# Receive_V1_Sch.net
KiCad netlist of a schematic drawn in Altium Designer
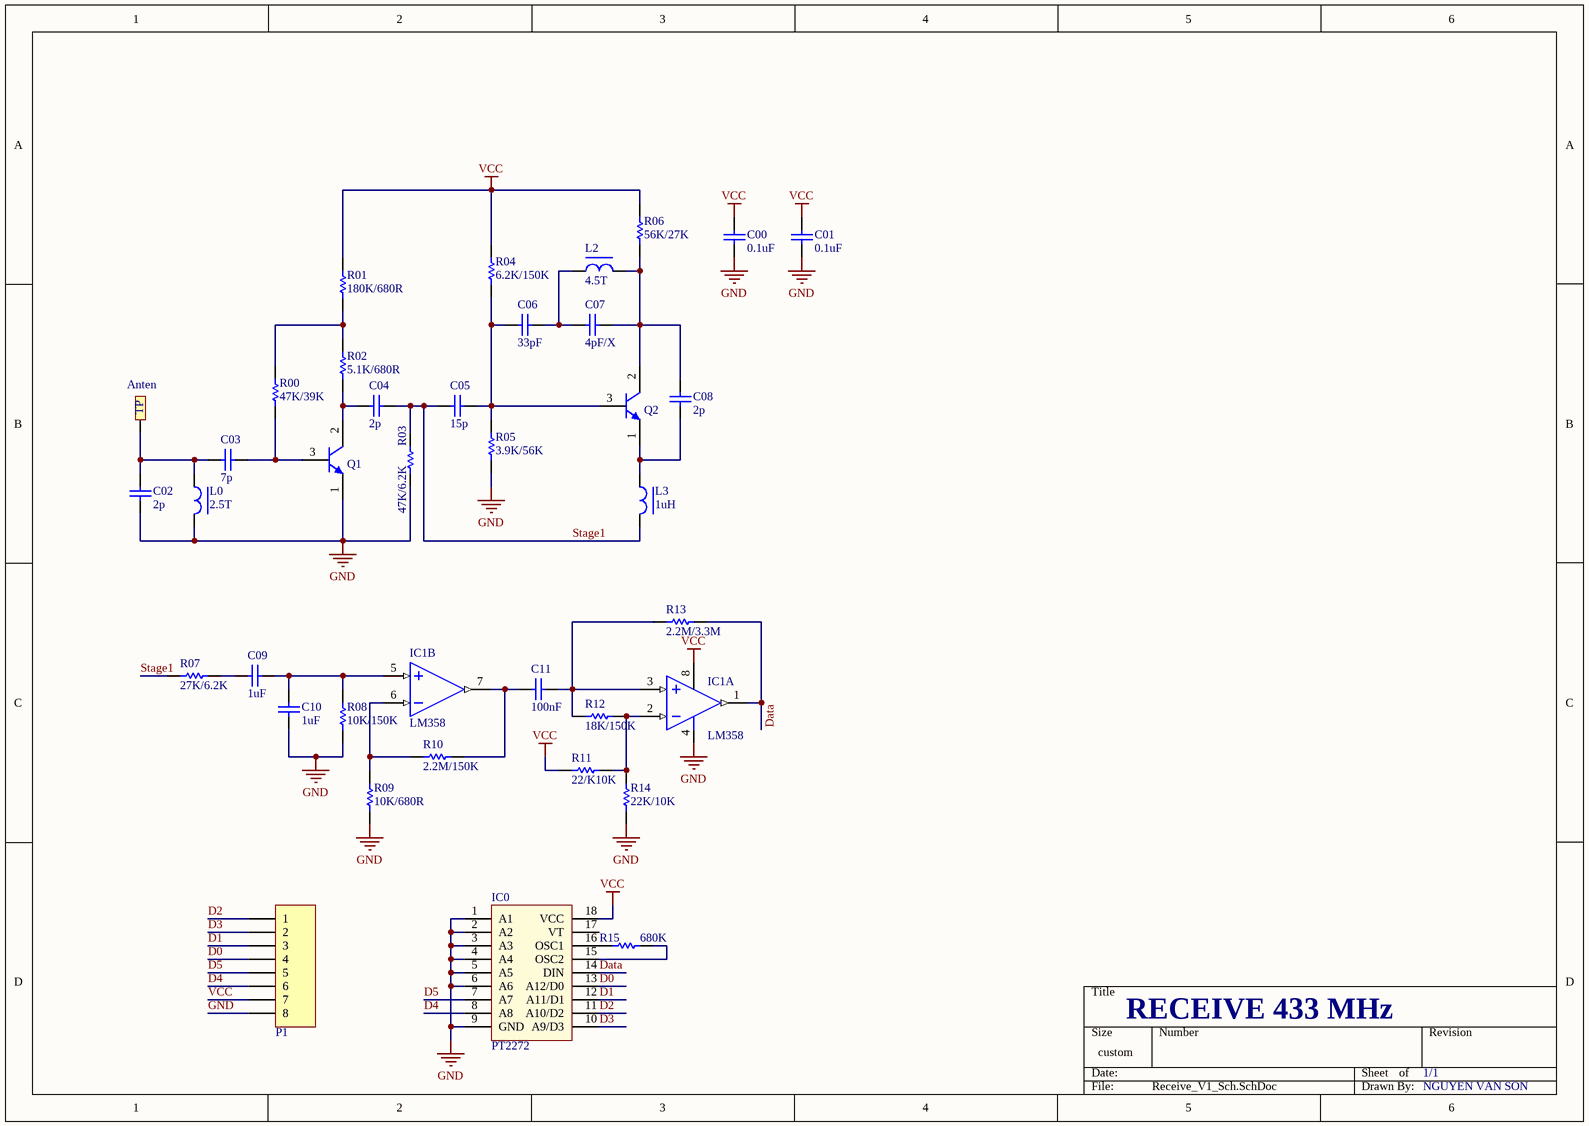
[diagram p0: Receive_V1_Sch.SchDoc]

(export (version "E")
  (design (tool "Eeschema 10.0.6"))
  (components
    (comp (ref "Anten")
      (value "Test Point")
      (footprint "TP")
      (libsource (lib "PIF_Library") (part "Test Point"))
    )
    (comp (ref "C00")
      (value "0.1uF")
      (footprint "CAP-SM-0603")
      (description "Capacitor")
      (fields (field (name "Comment") "Cap Non-Pol SMD"))
      (libsource (lib "PIF_Library") (part "Cap Non-Pol SMD"))
    )
    (comp (ref "C01")
      (value "0.1uF")
      (footprint "CAP-SM-0603")
      (description "Capacitor")
      (fields (field (name "Comment") "Cap Non-Pol SMD"))
      (libsource (lib "PIF_Library") (part "Cap Non-Pol SMD"))
    )
    (comp (ref "C02")
      (value "2p")
      (footprint "CAP-SM-0603")
      (description "Capacitor")
      (fields (field (name "Comment") "Cap Non-Pol SMD"))
      (libsource (lib "PIF_Library") (part "Cap Non-Pol SMD"))
    )
    (comp (ref "C03")
      (value "7p")
      (footprint "CAP-SM-0805")
      (description "Capacitor")
      (fields (field (name "Comment") "Cap Non-Pol SMD"))
      (libsource (lib "PIF_Library") (part "Cap Non-Pol SMD"))
    )
    (comp (ref "C04")
      (value "2p")
      (footprint "CAP-SM-0603")
      (description "Capacitor")
      (fields (field (name "Comment") "Cap Non-Pol SMD"))
      (libsource (lib "PIF_Library") (part "Cap Non-Pol SMD"))
    )
    (comp (ref "C05")
      (value "15p")
      (footprint "CAP-SM-0603")
      (description "Capacitor")
      (fields (field (name "Comment") "Cap Non-Pol SMD"))
      (libsource (lib "PIF_Library") (part "Cap Non-Pol SMD"))
    )
    (comp (ref "C06")
      (value "33pF")
      (footprint "CAP-SM-0603")
      (description "Capacitor")
      (fields (field (name "Comment") "Cap Non-Pol SMD"))
      (libsource (lib "PIF_Library") (part "Cap Non-Pol SMD"))
    )
    (comp (ref "C07")
      (value "4pF/X")
      (footprint "CAP-SM-0603")
      (description "Capacitor")
      (fields (field (name "Comment") "Cap Non-Pol SMD"))
      (libsource (lib "PIF_Library") (part "Cap Non-Pol SMD"))
    )
    (comp (ref "C08")
      (value "2p")
      (footprint "CAP-SM-0603")
      (description "Capacitor")
      (fields (field (name "Comment") "Cap Non-Pol SMD"))
      (libsource (lib "PIF_Library") (part "Cap Non-Pol SMD"))
    )
    (comp (ref "C09")
      (value "1uF")
      (footprint "CAP-SM-0603")
      (description "Capacitor")
      (fields (field (name "Comment") "Cap Non-Pol SMD"))
      (libsource (lib "PIF_Library") (part "Cap Non-Pol SMD"))
    )
    (comp (ref "C10")
      (value "1uF")
      (footprint "CAP-SM-0603")
      (description "Capacitor")
      (fields (field (name "Comment") "Cap Non-Pol SMD"))
      (libsource (lib "PIF_Library") (part "Cap Non-Pol SMD"))
    )
    (comp (ref "C11")
      (value "100nF")
      (footprint "CAP-SM-0603")
      (description "Capacitor")
      (fields (field (name "Comment") "Cap Non-Pol SMD"))
      (libsource (lib "PIF_Library") (part "Cap Non-Pol SMD"))
    )
    (comp (ref "IC0")
      (value "PT2272")
      (footprint "DIP18")
      (description "Remote Control Decoder")
      (libsource (lib "TechMT.VN_Lib_Project v2") (part "PT2272"))
    )
    (comp (ref "IC1")
      (value "LM358")
      (footprint "SOp 8")
      (description "Low-Power Dual Operational Amplifier")
      (libsource (lib "TechMT.VN_Lib_Project v2") (part "LM358"))
    )
    (comp (ref "L0")
      (value "2.5T")
      (footprint "L-DIP-M-5.3")
      (description "Inductor")
      (libsource (lib "TechMT.VN_Lib_Project v2") (part "L-DIP-1"))
    )
    (comp (ref "L2")
      (value "4.5T")
      (footprint "L-DIP-M-5.3")
      (description "Inductor")
      (libsource (lib "TechMT.VN_Lib_Project v2") (part "L-DIP-1"))
    )
    (comp (ref "L3")
      (value "1uH")
      (footprint "RES-SMD-0805")
      (description "Inductor")
      (libsource (lib "TechMT.VN_Lib_Project v2") (part "L-DIP-1"))
    )
    (comp (ref "P1")
      (value "Header 8")
      (footprint "JP8")
      (description "Header, 8-Pin")
      (fields (field (name "PUBLISHER") "Altium Limited"))
      (libsource (lib "PIF_Library") (part "Header 8"))
    )
    (comp (ref "Q1")
      (value "C1815")
      (footprint "SOT23B")
      (description "NPN Bipolar Transistor")
      (libsource (lib "PIF_Library") (part "C1815"))
    )
    (comp (ref "Q2")
      (value "C1815")
      (footprint "SOT23B")
      (description "NPN Bipolar Transistor")
      (libsource (lib "PIF_Library") (part "C1815"))
    )
    (comp (ref "R00")
      (value "47K/39K")
      (footprint "RES-SM-0603")
      (description "Resistor")
      (fields (field (name "Comment") "RESISTOR SMD"))
      (libsource (lib "PIF_Library") (part "RESISTOR SMD"))
    )
    (comp (ref "R01")
      (value "180K/680R")
      (footprint "RES-SM-0603")
      (description "Resistor")
      (fields (field (name "Comment") "RESISTOR SMD"))
      (libsource (lib "PIF_Library") (part "RESISTOR SMD"))
    )
    (comp (ref "R02")
      (value "5.1K/680R")
      (footprint "RES-SM-0805")
      (description "Resistor")
      (fields (field (name "Comment") "RESISTOR SMD"))
      (libsource (lib "PIF_Library") (part "RESISTOR SMD"))
    )
    (comp (ref "R03")
      (value "47K/6.2K")
      (footprint "RES-SM-0603")
      (description "Resistor")
      (fields (field (name "Comment") "RESISTOR SMD"))
      (libsource (lib "PIF_Library") (part "RESISTOR SMD"))
    )
    (comp (ref "R04")
      (value "6.2K/150K")
      (footprint "RES-SM-0805")
      (description "Resistor")
      (fields (field (name "Comment") "RESISTOR SMD"))
      (libsource (lib "PIF_Library") (part "RESISTOR SMD"))
    )
    (comp (ref "R05")
      (value "3.9K/56K")
      (footprint "RES-SM-0805")
      (description "Resistor")
      (fields (field (name "Comment") "RESISTOR SMD"))
      (libsource (lib "PIF_Library") (part "RESISTOR SMD"))
    )
    (comp (ref "R06")
      (value "56K/27K")
      (footprint "RES-SM-0603")
      (description "Resistor")
      (fields (field (name "Comment") "RESISTOR SMD"))
      (libsource (lib "PIF_Library") (part "RESISTOR SMD"))
    )
    (comp (ref "R07")
      (value "27K/6.2K")
      (footprint "RES-SM-0603")
      (description "Resistor")
      (fields (field (name "Comment") "RESISTOR SMD"))
      (libsource (lib "PIF_Library") (part "RESISTOR SMD"))
    )
    (comp (ref "R08")
      (value "10K/150K")
      (footprint "RES-SM-0603")
      (description "Resistor")
      (fields (field (name "Comment") "RESISTOR SMD"))
      (libsource (lib "PIF_Library") (part "RESISTOR SMD"))
    )
    (comp (ref "R09")
      (value "10K/680R")
      (footprint "RES-SM-0603")
      (description "Resistor")
      (fields (field (name "Comment") "RESISTOR SMD"))
      (libsource (lib "PIF_Library") (part "RESISTOR SMD"))
    )
    (comp (ref "R10")
      (value "2.2M/150K")
      (footprint "RES-SM-0603")
      (description "Resistor")
      (fields (field (name "Comment") "RESISTOR SMD"))
      (libsource (lib "PIF_Library") (part "RESISTOR SMD"))
    )
    (comp (ref "R11")
      (value "22/K10K")
      (footprint "RES-SM-0603")
      (description "Resistor")
      (fields (field (name "Comment") "RESISTOR SMD"))
      (libsource (lib "PIF_Library") (part "RESISTOR SMD"))
    )
    (comp (ref "R12")
      (value "18K/150K")
      (footprint "RES-SM-0603")
      (description "Resistor")
      (fields (field (name "Comment") "RESISTOR SMD"))
      (libsource (lib "PIF_Library") (part "RESISTOR SMD"))
    )
    (comp (ref "R13")
      (value "2.2M/3.3M")
      (footprint "RES-SM-0603")
      (description "Resistor")
      (fields (field (name "Comment") "RESISTOR SMD"))
      (libsource (lib "PIF_Library") (part "RESISTOR SMD"))
    )
    (comp (ref "R14")
      (value "RESISTOR SMD")
      (footprint "RES-SM-0603")
      (description "Resistor")
      (fields (field (name "R?") "22K/10K"))
      (libsource (lib "PIF_Library") (part "RESISTOR SMD"))
    )
    (comp (ref "R15")
      (value "680K")
      (footprint "RES-SM-0805")
      (description "Resistor")
      (fields (field (name "Comment") "RESISTOR SMD"))
      (libsource (lib "PIF_Library") (part "RESISTOR SMD"))
    )
  )
  (nets
    (net (code "1") (name "/D0") (class "Default")
      (node (ref "IC0") (pin "13") (pinfunction "A12/D0_13") (pintype "passive"))
      (node (ref "P1") (pin "4") (pinfunction "4_4") (pintype "passive"))
    )
    (net (code "2") (name "/D1") (class "Default")
      (node (ref "IC0") (pin "12") (pinfunction "A11/D1_12") (pintype "passive"))
      (node (ref "P1") (pin "3") (pinfunction "3_3") (pintype "passive"))
    )
    (net (code "3") (name "/D2") (class "Default")
      (node (ref "IC0") (pin "11") (pinfunction "A10/D2_11") (pintype "passive"))
      (node (ref "P1") (pin "1") (pinfunction "1_1") (pintype "passive"))
    )
    (net (code "4") (name "/D3") (class "Default")
      (node (ref "IC0") (pin "10") (pinfunction "A9/D3_10") (pintype "passive"))
      (node (ref "P1") (pin "2") (pinfunction "2_2") (pintype "passive"))
    )
    (net (code "5") (name "/D4") (class "Default")
      (node (ref "IC0") (pin "8") (pinfunction "A8_8") (pintype "passive"))
      (node (ref "P1") (pin "6") (pinfunction "6_6") (pintype "passive"))
    )
    (net (code "6") (name "/D5") (class "Default")
      (node (ref "IC0") (pin "7") (pinfunction "A7_7") (pintype "passive"))
      (node (ref "P1") (pin "5") (pinfunction "5_5") (pintype "passive"))
    )
    (net (code "7") (name "/Data") (class "Default")
      (node (ref "IC0") (pin "14") (pinfunction "DIN_14") (pintype "passive"))
      (node (ref "IC1") (pin "1") (pinfunction "OUT_1") (pintype "output"))
      (node (ref "R13") (pin "2") (pinfunction "2_2") (pintype "passive"))
    )
    (net (code "8") (name "/Stage1") (class "Default")
      (node (ref "C04") (pin "1") (pinfunction "1_1") (pintype "passive"))
      (node (ref "C05") (pin "2") (pinfunction "2_2") (pintype "passive"))
      (node (ref "L3") (pin "2") (pinfunction "2_2") (pintype "passive"))
      (node (ref "R03") (pin "1") (pinfunction "1_1") (pintype "passive"))
      (node (ref "R07") (pin "2") (pinfunction "2_2") (pintype "passive"))
    )
    (net (code "9") (name "GND") (class "Default")
      (node (ref "C00") (pin "1") (pinfunction "1_1") (pintype "passive"))
      (node (ref "C01") (pin "1") (pinfunction "1_1") (pintype "passive"))
      (node (ref "C02") (pin "1") (pinfunction "1_1") (pintype "passive"))
      (node (ref "C10") (pin "2") (pinfunction "2_2") (pintype "passive"))
      (node (ref "IC0") (pin "1") (pinfunction "A1_1") (pintype "passive"))
      (node (ref "IC0") (pin "2") (pinfunction "A2_2") (pintype "passive"))
      (node (ref "IC0") (pin "3") (pinfunction "A3_3") (pintype "passive"))
      (node (ref "IC0") (pin "4") (pinfunction "A4_4") (pintype "passive"))
      (node (ref "IC0") (pin "5") (pinfunction "A5_5") (pintype "passive"))
      (node (ref "IC0") (pin "6") (pinfunction "A6_6") (pintype "passive"))
      (node (ref "IC0") (pin "9") (pinfunction "GND_9") (pintype "passive"))
      (node (ref "IC1") (pin "4") (pinfunction "-V_4") (pintype "passive"))
      (node (ref "L0") (pin "2") (pinfunction "2_2") (pintype "passive"))
      (node (ref "P1") (pin "8") (pinfunction "8_8") (pintype "passive"))
      (node (ref "Q1") (pin "1") (pinfunction "E_1") (pintype "passive"))
      (node (ref "R03") (pin "2") (pinfunction "2_2") (pintype "passive"))
      (node (ref "R05") (pin "2") (pinfunction "2_2") (pintype "passive"))
      (node (ref "R08") (pin "2") (pinfunction "2_2") (pintype "passive"))
      (node (ref "R09") (pin "2") (pinfunction "2_2") (pintype "passive"))
      (node (ref "R14") (pin "2") (pinfunction "2_2") (pintype "passive"))
    )
    (net (code "10") (name "Net-(Anten-0)") (class "Default")
      (node (ref "Anten") (pin "TP1") (pinfunction "0_TP1") (pintype "passive"))
      (node (ref "C02") (pin "2") (pinfunction "2_2") (pintype "passive"))
      (node (ref "C03") (pin "2") (pinfunction "2_2") (pintype "passive"))
      (node (ref "L0") (pin "1") (pinfunction "1_1") (pintype "passive"))
    )
    (net (code "11") (name "Net-(C06-Pad1)") (class "Default")
      (node (ref "C06") (pin "1") (pinfunction "1_1") (pintype "passive"))
      (node (ref "C07") (pin "2") (pinfunction "2_2") (pintype "passive"))
      (node (ref "L2") (pin "1") (pinfunction "1_1") (pintype "passive"))
    )
    (net (code "12") (name "Net-(C09-Pad2)") (class "Default")
      (node (ref "C09") (pin "2") (pinfunction "2_2") (pintype "passive"))
      (node (ref "R07") (pin "1") (pinfunction "1_1") (pintype "passive"))
    )
    (net (code "13") (name "Net-(IC0-OSC1)") (class "Default")
      (node (ref "IC0") (pin "16") (pinfunction "OSC1_16") (pintype "passive"))
      (node (ref "R15") (pin "1") (pinfunction "1_1") (pintype "passive"))
    )
    (net (code "14") (name "Net-(IC0-OSC2)") (class "Default")
      (node (ref "IC0") (pin "15") (pinfunction "OSC2_15") (pintype "passive"))
      (node (ref "R15") (pin "2") (pinfunction "2_2") (pintype "passive"))
    )
    (net (code "15") (name "Net-(IC1A-IN+)") (class "Default")
      (node (ref "C11") (pin "1") (pinfunction "1_1") (pintype "passive"))
      (node (ref "IC1") (pin "3") (pinfunction "IN+_3") (pintype "input"))
      (node (ref "R12") (pin "2") (pinfunction "2_2") (pintype "passive"))
      (node (ref "R13") (pin "1") (pinfunction "1_1") (pintype "passive"))
    )
    (net (code "16") (name "Net-(IC1A-IN-)") (class "Default")
      (node (ref "IC1") (pin "2") (pinfunction "IN-_2") (pintype "input"))
      (node (ref "R11") (pin "1") (pinfunction "1_1") (pintype "passive"))
      (node (ref "R12") (pin "1") (pinfunction "1_1") (pintype "passive"))
      (node (ref "R14") (pin "1") (pinfunction "1_1") (pintype "passive"))
    )
    (net (code "17") (name "Net-(IC1B-IN+)") (class "Default")
      (node (ref "C09") (pin "1") (pinfunction "1_1") (pintype "passive"))
      (node (ref "C10") (pin "1") (pinfunction "1_1") (pintype "passive"))
      (node (ref "IC1") (pin "5") (pinfunction "IN+_5") (pintype "input"))
      (node (ref "R08") (pin "1") (pinfunction "1_1") (pintype "passive"))
    )
    (net (code "18") (name "Net-(IC1B-IN-)") (class "Default")
      (node (ref "IC1") (pin "6") (pinfunction "IN-_6") (pintype "input"))
      (node (ref "R09") (pin "1") (pinfunction "1_1") (pintype "passive"))
      (node (ref "R10") (pin "1") (pinfunction "1_1") (pintype "passive"))
    )
    (net (code "19") (name "Net-(IC1B-OUT)") (class "Default")
      (node (ref "C11") (pin "2") (pinfunction "2_2") (pintype "passive"))
      (node (ref "IC1") (pin "7") (pinfunction "OUT_7") (pintype "output"))
      (node (ref "R10") (pin "2") (pinfunction "2_2") (pintype "passive"))
    )
    (net (code "20") (name "Net-(Q1-B)") (class "Default")
      (node (ref "C03") (pin "1") (pinfunction "1_1") (pintype "passive"))
      (node (ref "Q1") (pin "3") (pinfunction "B_3") (pintype "passive"))
      (node (ref "R00") (pin "2") (pinfunction "2_2") (pintype "passive"))
    )
    (net (code "21") (name "Net-(Q1-C)") (class "Default")
      (node (ref "C04") (pin "2") (pinfunction "2_2") (pintype "passive"))
      (node (ref "Q1") (pin "2") (pinfunction "C_2") (pintype "passive"))
      (node (ref "R02") (pin "2") (pinfunction "2_2") (pintype "passive"))
    )
    (net (code "22") (name "Net-(Q2-B)") (class "Default")
      (node (ref "C05") (pin "1") (pinfunction "1_1") (pintype "passive"))
      (node (ref "C06") (pin "2") (pinfunction "2_2") (pintype "passive"))
      (node (ref "Q2") (pin "3") (pinfunction "B_3") (pintype "passive"))
      (node (ref "R04") (pin "2") (pinfunction "2_2") (pintype "passive"))
      (node (ref "R05") (pin "1") (pinfunction "1_1") (pintype "passive"))
    )
    (net (code "23") (name "Net-(Q2-C)") (class "Default")
      (node (ref "C07") (pin "1") (pinfunction "1_1") (pintype "passive"))
      (node (ref "C08") (pin "1") (pinfunction "1_1") (pintype "passive"))
      (node (ref "L2") (pin "2") (pinfunction "2_2") (pintype "passive"))
      (node (ref "Q2") (pin "2") (pinfunction "C_2") (pintype "passive"))
      (node (ref "R06") (pin "2") (pinfunction "2_2") (pintype "passive"))
    )
    (net (code "24") (name "Net-(Q2-E)") (class "Default")
      (node (ref "C08") (pin "2") (pinfunction "2_2") (pintype "passive"))
      (node (ref "L3") (pin "1") (pinfunction "1_1") (pintype "passive"))
      (node (ref "Q2") (pin "1") (pinfunction "E_1") (pintype "passive"))
    )
    (net (code "25") (name "Net-(R00-Pad1)") (class "Default")
      (node (ref "R00") (pin "1") (pinfunction "1_1") (pintype "passive"))
      (node (ref "R01") (pin "2") (pinfunction "2_2") (pintype "passive"))
      (node (ref "R02") (pin "1") (pinfunction "1_1") (pintype "passive"))
    )
    (net (code "26") (name "VCC") (class "Default")
      (node (ref "C00") (pin "2") (pinfunction "2_2") (pintype "passive"))
      (node (ref "C01") (pin "2") (pinfunction "2_2") (pintype "passive"))
      (node (ref "IC0") (pin "18") (pinfunction "VCC_18") (pintype "passive"))
      (node (ref "IC1") (pin "8") (pinfunction "+V_8") (pintype "passive"))
      (node (ref "P1") (pin "7") (pinfunction "7_7") (pintype "passive"))
      (node (ref "R01") (pin "1") (pinfunction "1_1") (pintype "passive"))
      (node (ref "R04") (pin "1") (pinfunction "1_1") (pintype "passive"))
      (node (ref "R06") (pin "1") (pinfunction "1_1") (pintype "passive"))
      (node (ref "R11") (pin "2") (pinfunction "2_2") (pintype "passive"))
    )
    (net (code "27") (name "unconnected-(IC0-VT-Pad17)") (class "Default")
      (node (ref "IC0") (pin "17") (pinfunction "VT_17") (pintype "passive"))
    )
  )
)
